# THC-schematic.net
KiCad netlist of a schematic drawn in EAGLE
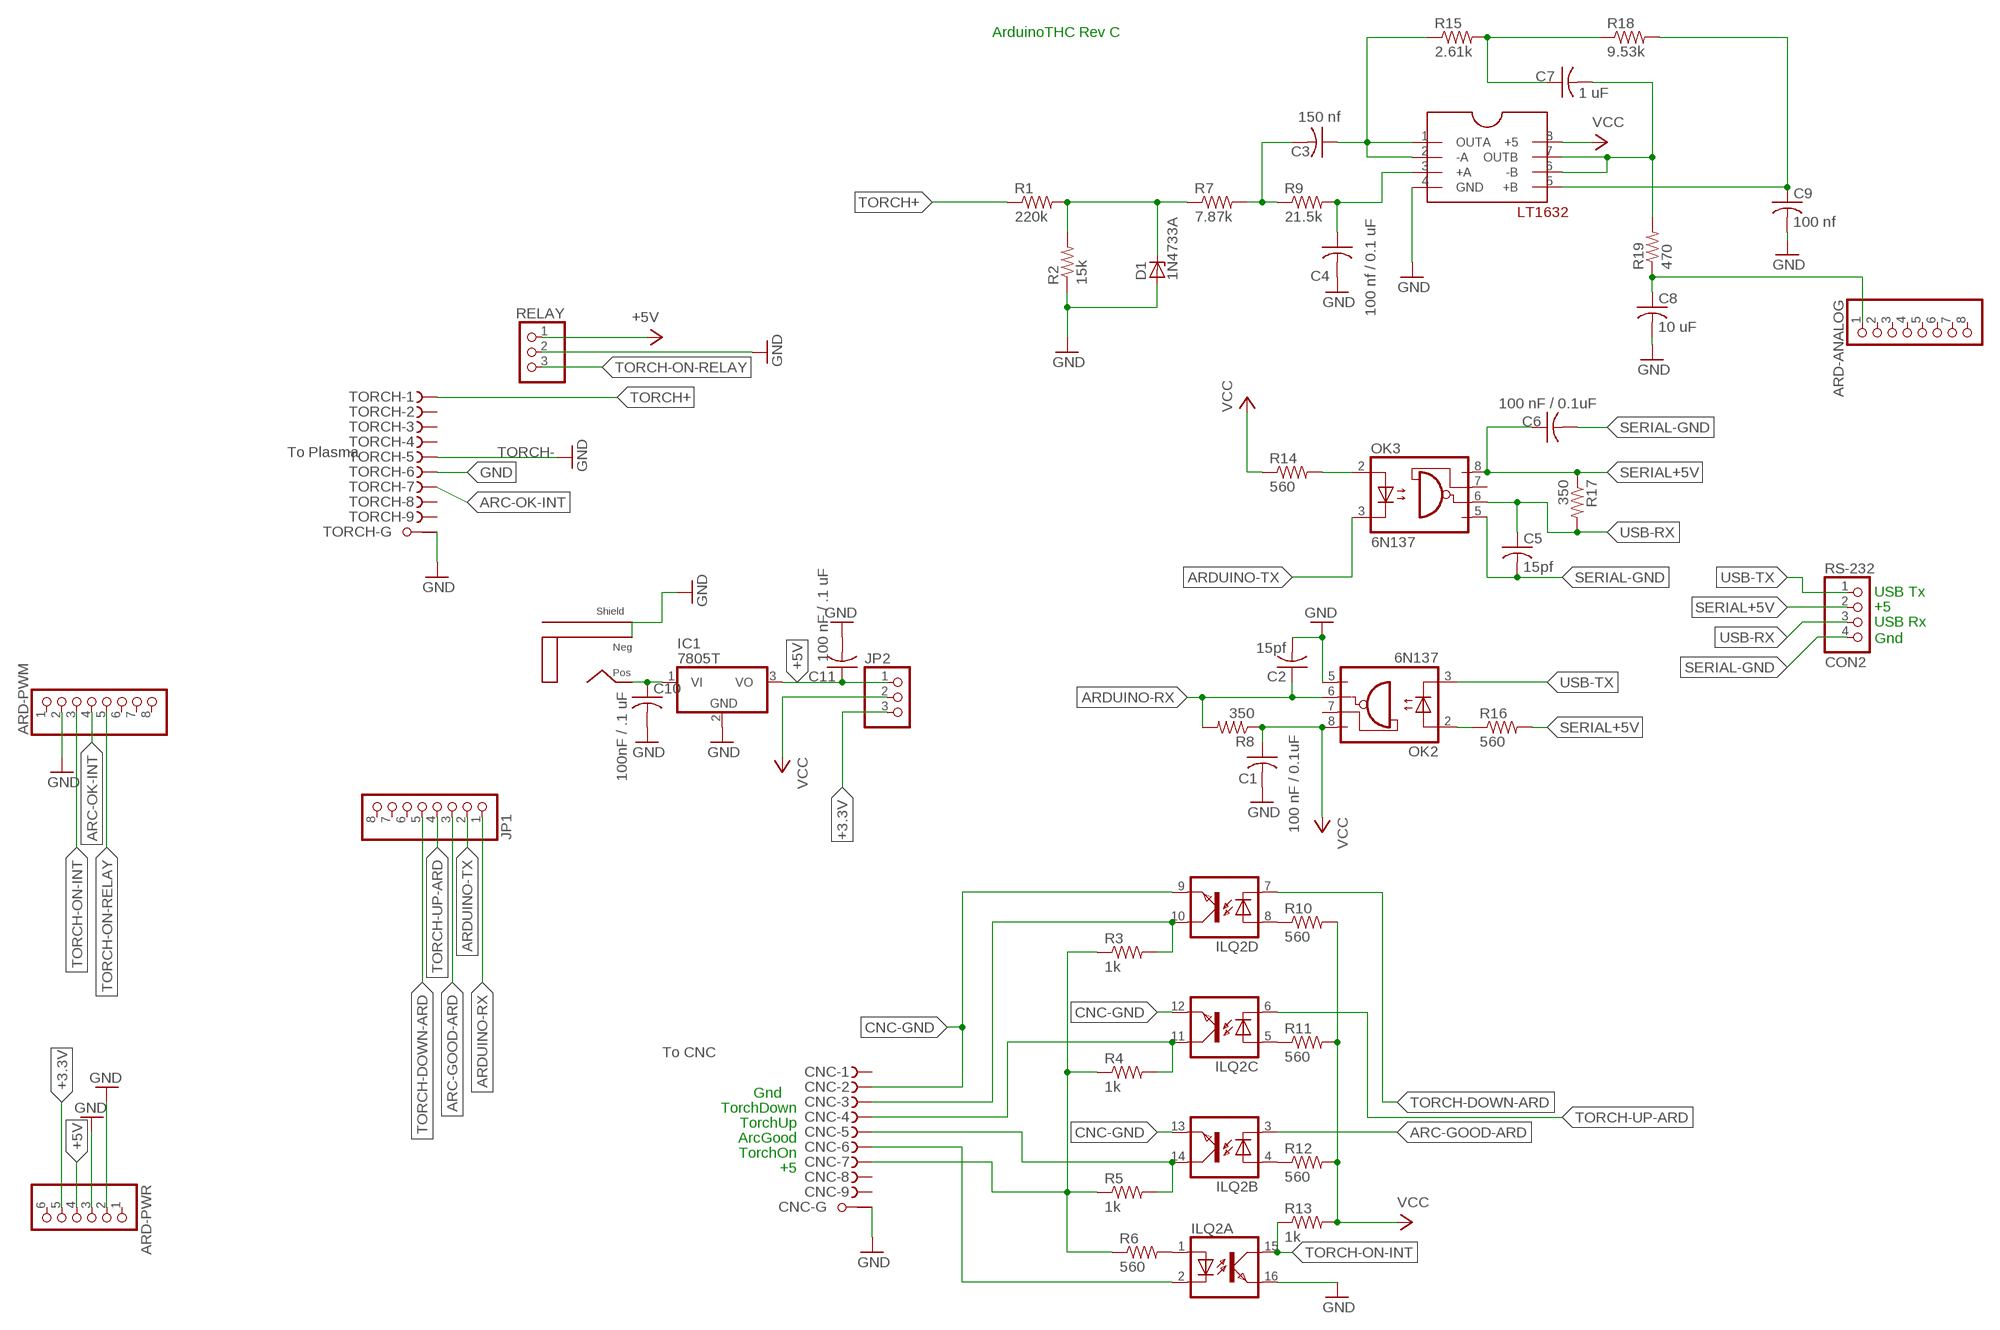
[diagram p0: schematic, sheet 1]

(export (version "E")
  (design (tool "Eeschema 10.0.6"))
  (components
    (comp (ref "ARD-ANALOG")
      (value "PINHD-1X8")
      (footprint "eagle-import:1X08")
      (libsource (lib "eagle-import") (part "PINHD-1X8"))
    )
    (comp (ref "ARD-PWM")
      (value "PINHD-1X8")
      (footprint "eagle-import:1X08")
      (libsource (lib "eagle-import") (part "PINHD-1X8"))
    )
    (comp (ref "ARD-PWR")
      (value "PINHD-1X6")
      (footprint "eagle-import:1X06")
      (libsource (lib "eagle-import") (part "PINHD-1X6"))
    )
    (comp (ref "C1")
      (value "100 nF / 0.1uF")
      (footprint "eagle-import:C025-025X050")
      (libsource (lib "eagle-import") (part "C-US025-025X050"))
    )
    (comp (ref "C2")
      (value "15pf")
      (footprint "eagle-import:C025-025X050")
      (libsource (lib "eagle-import") (part "C-US025-025X050"))
    )
    (comp (ref "C3")
      (value "150 nf")
      (footprint "eagle-import:C025-025X050")
      (libsource (lib "eagle-import") (part "C-US025-025X050"))
    )
    (comp (ref "C4")
      (value "100 nf / 0.1 uF")
      (footprint "eagle-import:C025-025X050")
      (libsource (lib "eagle-import") (part "C-US025-025X050"))
    )
    (comp (ref "C5")
      (value "15pf")
      (footprint "eagle-import:C025-025X050")
      (libsource (lib "eagle-import") (part "C-US025-025X050"))
    )
    (comp (ref "C6")
      (value "100 nF / 0.1uF")
      (footprint "eagle-import:C025-025X050")
      (libsource (lib "eagle-import") (part "C-US025-025X050"))
    )
    (comp (ref "C7")
      (value "1 uF")
      (footprint "eagle-import:C025-025X050")
      (libsource (lib "eagle-import") (part "C-US025-025X050"))
    )
    (comp (ref "C8")
      (value "10 uF")
      (footprint "eagle-import:C025-025X050")
      (libsource (lib "eagle-import") (part "C-US025-025X050"))
    )
    (comp (ref "C9")
      (value "100 nf")
      (footprint "eagle-import:C025-025X050")
      (libsource (lib "eagle-import") (part "C-US025-025X050"))
    )
    (comp (ref "C10")
      (value "100nF / .1 uF")
      (footprint "eagle-import:C025-025X050")
      (libsource (lib "eagle-import") (part "C-US025-025X050"))
    )
    (comp (ref "C11")
      (value "100 nF / .1 uF")
      (footprint "eagle-import:C025-025X050")
      (libsource (lib "eagle-import") (part "C-US025-025X050"))
    )
    (comp (ref "CNC")
      (value "F09HPS")
      (footprint "eagle-import:F09HP")
      (libsource (lib "eagle-import") (part "F09HPS"))
    )
    (comp (ref "D1")
      (value "1N4733A")
      (footprint "eagle-import:DO41Z10")
      (libsource (lib "eagle-import") (part "ZPY"))
    )
    (comp (ref "IC1")
      (value "7805T")
      (footprint "eagle-import:TO220H")
      (libsource (lib "eagle-import") (part "78T05"))
    )
    (comp (ref "ILQ2")
      (value "ILQ1")
      (footprint "eagle-import:DIL16")
      (fields (field (name "MF") "VISHAY/TELEFUNKEN"))
      (libsource (lib "eagle-import") (part "ILQ1"))
    )
    (comp (ref "J1")
      (value "2.1MM-PLUG-PCB-MNT")
      (footprint "eagle-import:2.1MM-PLUG")
      (libsource (lib "eagle-import") (part "2.1MM-PLUG-PCB-MNT"))
    )
    (comp (ref "JP1")
      (value "PINHD-1X8")
      (footprint "eagle-import:1X08")
      (libsource (lib "eagle-import") (part "PINHD-1X8"))
    )
    (comp (ref "JP2")
      (value "PINHD-1X3")
      (footprint "eagle-import:1X03")
      (libsource (lib "eagle-import") (part "PINHD-1X3"))
    )
    (comp (ref "OK2")
      (value "6N137")
      (footprint "eagle-import:DIL08")
      (libsource (lib "eagle-import") (part "6N137"))
    )
    (comp (ref "OK3")
      (value "6N137")
      (footprint "eagle-import:DIL08")
      (libsource (lib "eagle-import") (part "6N137"))
    )
    (comp (ref "R1")
      (value "220k")
      (footprint "eagle-import:0207_7")
      (libsource (lib "eagle-import") (part "R-US_0207/7"))
    )
    (comp (ref "R2")
      (value "15k")
      (footprint "eagle-import:0207_7")
      (libsource (lib "eagle-import") (part "R-US_0207/7"))
    )
    (comp (ref "R3")
      (value "1k")
      (footprint "eagle-import:0207_7")
      (libsource (lib "eagle-import") (part "R-US_0207/7"))
    )
    (comp (ref "R4")
      (value "1k")
      (footprint "eagle-import:0207_7")
      (libsource (lib "eagle-import") (part "R-US_0207/7"))
    )
    (comp (ref "R5")
      (value "1k")
      (footprint "eagle-import:0207_7")
      (libsource (lib "eagle-import") (part "R-US_0207/7"))
    )
    (comp (ref "R6")
      (value "560")
      (footprint "eagle-import:0207_7")
      (libsource (lib "eagle-import") (part "R-US_0207/7"))
    )
    (comp (ref "R7")
      (value "7.87k")
      (footprint "eagle-import:0207_7")
      (libsource (lib "eagle-import") (part "R-US_0207/7"))
    )
    (comp (ref "R8")
      (value "350")
      (footprint "eagle-import:0207_7")
      (libsource (lib "eagle-import") (part "R-US_0207/7"))
    )
    (comp (ref "R9")
      (value "21.5k")
      (footprint "eagle-import:0207_7")
      (libsource (lib "eagle-import") (part "R-US_0207/7"))
    )
    (comp (ref "R10")
      (value "560")
      (footprint "eagle-import:0207_7")
      (libsource (lib "eagle-import") (part "R-US_0207/7"))
    )
    (comp (ref "R11")
      (value "560")
      (footprint "eagle-import:0207_7")
      (libsource (lib "eagle-import") (part "R-US_0207/7"))
    )
    (comp (ref "R12")
      (value "560")
      (footprint "eagle-import:0207_7")
      (libsource (lib "eagle-import") (part "R-US_0207/7"))
    )
    (comp (ref "R13")
      (value "1k")
      (footprint "eagle-import:0207_7")
      (libsource (lib "eagle-import") (part "R-US_0207/7"))
    )
    (comp (ref "R14")
      (value "560")
      (footprint "eagle-import:0207_7")
      (libsource (lib "eagle-import") (part "R-US_0207/7"))
    )
    (comp (ref "R15")
      (value "2.61k")
      (footprint "eagle-import:0207_7")
      (libsource (lib "eagle-import") (part "R-US_0207/7"))
    )
    (comp (ref "R16")
      (value "560")
      (footprint "eagle-import:0207_7")
      (libsource (lib "eagle-import") (part "R-US_0207/7"))
    )
    (comp (ref "R17")
      (value "350")
      (footprint "eagle-import:0207_7")
      (libsource (lib "eagle-import") (part "R-US_0207/7"))
    )
    (comp (ref "R18")
      (value "9.53k")
      (footprint "eagle-import:0207_7")
      (libsource (lib "eagle-import") (part "R-US_0207/7"))
    )
    (comp (ref "R19")
      (value "470")
      (footprint "eagle-import:0207_7")
      (libsource (lib "eagle-import") (part "R-US_0207/7"))
    )
    (comp (ref "RELAY")
      (value "PINHD-1X3")
      (footprint "eagle-import:1X03")
      (libsource (lib "eagle-import") (part "PINHD-1X3"))
    )
    (comp (ref "RS-232")
      (value "CON2")
      (footprint "eagle-import:1X04")
      (libsource (lib "eagle-import") (part "PINHD-1X4"))
    )
    (comp (ref "TORCH")
      (value "F09HPS")
      (footprint "eagle-import:F09HP")
      (libsource (lib "eagle-import") (part "F09HPS"))
    )
    (comp (ref "U$1")
      (value "LT1632")
      (footprint "eagle-import:DIP08")
      (libsource (lib "eagle-import") (part "LT1632"))
    )
  )
  (nets
    (net (code "1") (name "+3.3V") (class "Default")
      (node (ref "ARD-PWR") (pin "5") (pinfunction "5_5") (pintype "passive"))
      (node (ref "JP2") (pin "3") (pinfunction "3_3") (pintype "passive"))
    )
    (net (code "2") (name "+5V") (class "Default")
      (node (ref "ARD-PWR") (pin "4") (pinfunction "4_4") (pintype "passive"))
      (node (ref "C11") (pin "1") (pinfunction "1_1") (pintype "passive"))
      (node (ref "IC1") (pin "3") (pinfunction "VO_3") (pintype "passive"))
      (node (ref "JP2") (pin "1") (pinfunction "1_1") (pintype "passive"))
      (node (ref "RELAY") (pin "1") (pinfunction "1_1") (pintype "passive"))
    )
    (net (code "3") (name "ARC-GOOD-ARD") (class "Default")
      (node (ref "ILQ2") (pin "3") (pinfunction "C_3") (pintype "passive"))
      (node (ref "JP1") (pin "3") (pinfunction "3_3") (pintype "passive"))
    )
    (net (code "4") (name "ARC-OK-INT") (class "Default")
      (node (ref "ARD-PWM") (pin "4") (pinfunction "4_4") (pintype "passive"))
      (node (ref "TORCH") (pin "7") (pinfunction "F_7") (pintype "passive"))
    )
    (net (code "5") (name "ARDUINO-RX") (class "Default")
      (node (ref "C2") (pin "1") (pinfunction "1_1") (pintype "passive"))
      (node (ref "JP1") (pin "1") (pinfunction "1_1") (pintype "passive"))
      (node (ref "OK2") (pin "6") (pinfunction "VO_6") (pintype "passive"))
      (node (ref "R8") (pin "2") (pinfunction "2_2") (pintype "passive"))
    )
    (net (code "6") (name "ARDUINO-TX") (class "Default")
      (node (ref "JP1") (pin "2") (pinfunction "2_2") (pintype "passive"))
      (node (ref "OK3") (pin "3") (pinfunction "C_3") (pintype "passive"))
    )
    (net (code "7") (name "CNC-GND") (class "Default")
      (node (ref "CNC") (pin "2") (pinfunction "F_2") (pintype "passive"))
      (node (ref "ILQ2") (pin "12") (pinfunction "EMIT_12") (pintype "passive"))
      (node (ref "ILQ2") (pin "13") (pinfunction "EMIT_13") (pintype "passive"))
      (node (ref "ILQ2") (pin "9") (pinfunction "EMIT_9") (pintype "passive"))
    )
    (net (code "8") (name "GND") (class "Default")
      (node (ref "ARD-PWM") (pin "2") (pinfunction "2_2") (pintype "passive"))
      (node (ref "ARD-PWR") (pin "2") (pinfunction "2_2") (pintype "passive"))
      (node (ref "ARD-PWR") (pin "3") (pinfunction "3_3") (pintype "passive"))
      (node (ref "C1") (pin "2") (pinfunction "2_2") (pintype "passive"))
      (node (ref "C10") (pin "2") (pinfunction "2_2") (pintype "passive"))
      (node (ref "C11") (pin "2") (pinfunction "2_2") (pintype "passive"))
      (node (ref "C2") (pin "2") (pinfunction "2_2") (pintype "passive"))
      (node (ref "C4") (pin "2") (pinfunction "2_2") (pintype "passive"))
      (node (ref "C8") (pin "2") (pinfunction "2_2") (pintype "passive"))
      (node (ref "C9") (pin "2") (pinfunction "2_2") (pintype "passive"))
      (node (ref "CNC") (pin "G1") (pinfunction "G1_G1") (pintype "passive"))
      (node (ref "D1") (pin "A") (pinfunction "A_A") (pintype "passive"))
      (node (ref "IC1") (pin "2") (pinfunction "GND_2") (pintype "passive"))
      (node (ref "ILQ2") (pin "16") (pinfunction "EMIT_16") (pintype "passive"))
      (node (ref "J1") (pin "P$NEG") (pinfunction "P$NEG_P$NEG") (pintype "bidirectional"))
      (node (ref "J1") (pin "P$SHLD") (pinfunction "P$SHLD_P$SHLD") (pintype "bidirectional"))
      (node (ref "OK2") (pin "5") (pinfunction "GND_5") (pintype "passive"))
      (node (ref "R2") (pin "1") (pinfunction "1_1") (pintype "passive"))
      (node (ref "RELAY") (pin "2") (pinfunction "2_2") (pintype "passive"))
      (node (ref "TORCH") (pin "5") (pinfunction "F_5") (pintype "passive"))
      (node (ref "TORCH") (pin "6") (pinfunction "F_6") (pintype "passive"))
      (node (ref "TORCH") (pin "G1") (pinfunction "G1_G1") (pintype "passive"))
      (node (ref "U$1") (pin "4") (pinfunction "GND_4") (pintype "bidirectional"))
    )
    (net (code "9") (name "Net-(ARD-ANALOG-Pad1)") (class "Default")
      (node (ref "ARD-ANALOG") (pin "1") (pinfunction "1_1") (pintype "passive"))
      (node (ref "C8") (pin "1") (pinfunction "1_1") (pintype "passive"))
      (node (ref "R19") (pin "1") (pinfunction "1_1") (pintype "passive"))
    )
    (net (code "10") (name "Net-(C3-Pad2)") (class "Default")
      (node (ref "C3") (pin "2") (pinfunction "2_2") (pintype "passive"))
      (node (ref "R7") (pin "2") (pinfunction "2_2") (pintype "passive"))
      (node (ref "R9") (pin "1") (pinfunction "1_1") (pintype "passive"))
    )
    (net (code "11") (name "Net-(C7-Pad1)") (class "Default")
      (node (ref "C7") (pin "1") (pinfunction "1_1") (pintype "passive"))
      (node (ref "R15") (pin "2") (pinfunction "2_2") (pintype "passive"))
      (node (ref "R18") (pin "1") (pinfunction "1_1") (pintype "passive"))
    )
    (net (code "12") (name "Net-(CNCC-F)") (class "Default")
      (node (ref "CNC") (pin "3") (pinfunction "F_3") (pintype "passive"))
      (node (ref "ILQ2") (pin "10") (pinfunction "COL_10") (pintype "passive"))
      (node (ref "R3") (pin "2") (pinfunction "2_2") (pintype "passive"))
    )
    (net (code "13") (name "Net-(CNCD-F)") (class "Default")
      (node (ref "CNC") (pin "4") (pinfunction "F_4") (pintype "passive"))
      (node (ref "ILQ2") (pin "11") (pinfunction "COL_11") (pintype "passive"))
      (node (ref "R4") (pin "2") (pinfunction "2_2") (pintype "passive"))
    )
    (net (code "14") (name "Net-(CNCE-F)") (class "Default")
      (node (ref "CNC") (pin "5") (pinfunction "F_5") (pintype "passive"))
      (node (ref "ILQ2") (pin "14") (pinfunction "COL_14") (pintype "passive"))
      (node (ref "R5") (pin "2") (pinfunction "2_2") (pintype "passive"))
    )
    (net (code "15") (name "Net-(CNCF-F)") (class "Default")
      (node (ref "CNC") (pin "6") (pinfunction "F_6") (pintype "passive"))
      (node (ref "ILQ2") (pin "2") (pinfunction "C_2") (pintype "passive"))
    )
    (net (code "16") (name "Net-(CNCG-F)") (class "Default")
      (node (ref "CNC") (pin "7") (pinfunction "F_7") (pintype "passive"))
      (node (ref "R3") (pin "1") (pinfunction "1_1") (pintype "passive"))
      (node (ref "R4") (pin "1") (pinfunction "1_1") (pintype "passive"))
      (node (ref "R5") (pin "1") (pinfunction "1_1") (pintype "passive"))
      (node (ref "R6") (pin "1") (pinfunction "1_1") (pintype "passive"))
    )
    (net (code "17") (name "Net-(D1-PadC)") (class "Default")
      (node (ref "D1") (pin "C") (pinfunction "C_C") (pintype "passive"))
      (node (ref "R1") (pin "2") (pinfunction "2_2") (pintype "passive"))
      (node (ref "R2") (pin "2") (pinfunction "2_2") (pintype "passive"))
      (node (ref "R7") (pin "1") (pinfunction "1_1") (pintype "passive"))
    )
    (net (code "18") (name "Net-(IC1-VI)") (class "Default")
      (node (ref "C10") (pin "1") (pinfunction "1_1") (pintype "passive"))
      (node (ref "IC1") (pin "1") (pinfunction "VI_1") (pintype "input"))
      (node (ref "J1") (pin "P$POS") (pinfunction "P$POS_P$POS") (pintype "bidirectional"))
    )
    (net (code "19") (name "Net-(ILQ2A-A)") (class "Default")
      (node (ref "ILQ2") (pin "1") (pinfunction "A_1") (pintype "passive"))
      (node (ref "R6") (pin "2") (pinfunction "2_2") (pintype "passive"))
    )
    (net (code "20") (name "Net-(ILQ2B-A)") (class "Default")
      (node (ref "ILQ2") (pin "4") (pinfunction "A_4") (pintype "passive"))
      (node (ref "R12") (pin "1") (pinfunction "1_1") (pintype "passive"))
    )
    (net (code "21") (name "Net-(ILQ2C-A)") (class "Default")
      (node (ref "ILQ2") (pin "5") (pinfunction "A_5") (pintype "passive"))
      (node (ref "R11") (pin "1") (pinfunction "1_1") (pintype "passive"))
    )
    (net (code "22") (name "Net-(ILQ2D-A)") (class "Default")
      (node (ref "ILQ2") (pin "8") (pinfunction "A_8") (pintype "passive"))
      (node (ref "R10") (pin "1") (pinfunction "1_1") (pintype "passive"))
    )
    (net (code "23") (name "Net-(OK2-A)") (class "Default")
      (node (ref "OK2") (pin "2") (pinfunction "A_2") (pintype "passive"))
      (node (ref "R16") (pin "1") (pinfunction "1_1") (pintype "passive"))
    )
    (net (code "24") (name "Net-(OK3-A)") (class "Default")
      (node (ref "OK3") (pin "2") (pinfunction "A_2") (pintype "passive"))
      (node (ref "R14") (pin "2") (pinfunction "2_2") (pintype "passive"))
    )
    (net (code "25") (name "Net-(U$1-+A)") (class "Default")
      (node (ref "C4") (pin "1") (pinfunction "1_1") (pintype "passive"))
      (node (ref "R9") (pin "2") (pinfunction "2_2") (pintype "passive"))
      (node (ref "U$1") (pin "3") (pinfunction "+A_3") (pintype "bidirectional"))
    )
    (net (code "26") (name "Net-(U$1-+B)") (class "Default")
      (node (ref "C9") (pin "1") (pinfunction "1_1") (pintype "passive"))
      (node (ref "R18") (pin "2") (pinfunction "2_2") (pintype "passive"))
      (node (ref "U$1") (pin "5") (pinfunction "+B_5") (pintype "bidirectional"))
    )
    (net (code "27") (name "Net-(U$1--A)") (class "Default")
      (node (ref "C3") (pin "1") (pinfunction "1_1") (pintype "passive"))
      (node (ref "R15") (pin "1") (pinfunction "1_1") (pintype "passive"))
      (node (ref "U$1") (pin "1") (pinfunction "OUTA_1") (pintype "bidirectional"))
      (node (ref "U$1") (pin "2") (pinfunction "-A_2") (pintype "bidirectional"))
    )
    (net (code "28") (name "Net-(U$1--B)") (class "Default")
      (node (ref "C7") (pin "2") (pinfunction "2_2") (pintype "passive"))
      (node (ref "R19") (pin "2") (pinfunction "2_2") (pintype "passive"))
      (node (ref "U$1") (pin "6") (pinfunction "-B_6") (pintype "bidirectional"))
      (node (ref "U$1") (pin "7") (pinfunction "OUTB_7") (pintype "bidirectional"))
    )
    (net (code "29") (name "SERIAL+5V") (class "Default")
      (node (ref "C6") (pin "1") (pinfunction "1_1") (pintype "passive"))
      (node (ref "OK3") (pin "8") (pinfunction "VCC_8") (pintype "passive"))
      (node (ref "R16") (pin "2") (pinfunction "2_2") (pintype "passive"))
      (node (ref "R17") (pin "1") (pinfunction "1_1") (pintype "passive"))
      (node (ref "RS-232") (pin "2") (pinfunction "2_2") (pintype "passive"))
    )
    (net (code "30") (name "SERIAL-GND") (class "Default")
      (node (ref "C5") (pin "2") (pinfunction "2_2") (pintype "passive"))
      (node (ref "C6") (pin "2") (pinfunction "2_2") (pintype "passive"))
      (node (ref "OK3") (pin "5") (pinfunction "GND_5") (pintype "passive"))
      (node (ref "RS-232") (pin "4") (pinfunction "4_4") (pintype "passive"))
    )
    (net (code "31") (name "TORCH+") (class "Default")
      (node (ref "R1") (pin "1") (pinfunction "1_1") (pintype "passive"))
      (node (ref "TORCH") (pin "1") (pinfunction "F_1") (pintype "passive"))
    )
    (net (code "32") (name "TORCH-DOWN-ARD") (class "Default")
      (node (ref "ILQ2") (pin "7") (pinfunction "C_7") (pintype "passive"))
      (node (ref "JP1") (pin "5") (pinfunction "5_5") (pintype "passive"))
    )
    (net (code "33") (name "TORCH-ON-INT") (class "Default")
      (node (ref "ARD-PWM") (pin "3") (pinfunction "3_3") (pintype "passive"))
      (node (ref "ILQ2") (pin "15") (pinfunction "COL_15") (pintype "passive"))
      (node (ref "R13") (pin "1") (pinfunction "1_1") (pintype "passive"))
    )
    (net (code "34") (name "TORCH-ON-RELAY") (class "Default")
      (node (ref "ARD-PWM") (pin "5") (pinfunction "5_5") (pintype "passive"))
      (node (ref "RELAY") (pin "3") (pinfunction "3_3") (pintype "passive"))
    )
    (net (code "35") (name "TORCH-UP-ARD") (class "Default")
      (node (ref "ILQ2") (pin "6") (pinfunction "C_6") (pintype "passive"))
      (node (ref "JP1") (pin "4") (pinfunction "4_4") (pintype "passive"))
    )
    (net (code "36") (name "USB-RX") (class "Default")
      (node (ref "C5") (pin "1") (pinfunction "1_1") (pintype "passive"))
      (node (ref "OK3") (pin "6") (pinfunction "VO_6") (pintype "passive"))
      (node (ref "R17") (pin "2") (pinfunction "2_2") (pintype "passive"))
      (node (ref "RS-232") (pin "3") (pinfunction "3_3") (pintype "passive"))
    )
    (net (code "37") (name "USB-TX") (class "Default")
      (node (ref "OK2") (pin "3") (pinfunction "C_3") (pintype "passive"))
      (node (ref "RS-232") (pin "1") (pinfunction "1_1") (pintype "passive"))
    )
    (net (code "38") (name "VCC") (class "Default")
      (node (ref "C1") (pin "1") (pinfunction "1_1") (pintype "passive"))
      (node (ref "JP2") (pin "2") (pinfunction "2_2") (pintype "passive"))
      (node (ref "OK2") (pin "8") (pinfunction "VCC_8") (pintype "passive"))
      (node (ref "R10") (pin "2") (pinfunction "2_2") (pintype "passive"))
      (node (ref "R11") (pin "2") (pinfunction "2_2") (pintype "passive"))
      (node (ref "R12") (pin "2") (pinfunction "2_2") (pintype "passive"))
      (node (ref "R13") (pin "2") (pinfunction "2_2") (pintype "passive"))
      (node (ref "R14") (pin "1") (pinfunction "1_1") (pintype "passive"))
      (node (ref "R8") (pin "1") (pinfunction "1_1") (pintype "passive"))
      (node (ref "U$1") (pin "8") (pinfunction "+5_8") (pintype "bidirectional"))
    )
    (net (code "39") (name "unconnected-(ARD-ANALOG-Pad2)") (class "Default")
      (node (ref "ARD-ANALOG") (pin "2") (pinfunction "2_2") (pintype "passive"))
    )
    (net (code "40") (name "unconnected-(ARD-ANALOG-Pad3)") (class "Default")
      (node (ref "ARD-ANALOG") (pin "3") (pinfunction "3_3") (pintype "passive"))
    )
    (net (code "41") (name "unconnected-(ARD-ANALOG-Pad4)") (class "Default")
      (node (ref "ARD-ANALOG") (pin "4") (pinfunction "4_4") (pintype "passive"))
    )
    (net (code "42") (name "unconnected-(ARD-ANALOG-Pad5)") (class "Default")
      (node (ref "ARD-ANALOG") (pin "5") (pinfunction "5_5") (pintype "passive"))
    )
    (net (code "43") (name "unconnected-(ARD-ANALOG-Pad6)") (class "Default")
      (node (ref "ARD-ANALOG") (pin "6") (pinfunction "6_6") (pintype "passive"))
    )
    (net (code "44") (name "unconnected-(ARD-ANALOG-Pad7)") (class "Default")
      (node (ref "ARD-ANALOG") (pin "7") (pinfunction "7_7") (pintype "passive"))
    )
    (net (code "45") (name "unconnected-(ARD-ANALOG-Pad8)") (class "Default")
      (node (ref "ARD-ANALOG") (pin "8") (pinfunction "8_8") (pintype "passive"))
    )
    (net (code "46") (name "unconnected-(ARD-PWM-Pad1)") (class "Default")
      (node (ref "ARD-PWM") (pin "1") (pinfunction "1_1") (pintype "passive"))
    )
    (net (code "47") (name "unconnected-(ARD-PWM-Pad6)") (class "Default")
      (node (ref "ARD-PWM") (pin "6") (pinfunction "6_6") (pintype "passive"))
    )
    (net (code "48") (name "unconnected-(ARD-PWM-Pad7)") (class "Default")
      (node (ref "ARD-PWM") (pin "7") (pinfunction "7_7") (pintype "passive"))
    )
    (net (code "49") (name "unconnected-(ARD-PWM-Pad8)") (class "Default")
      (node (ref "ARD-PWM") (pin "8") (pinfunction "8_8") (pintype "passive"))
    )
    (net (code "50") (name "unconnected-(ARD-PWR-Pad1)") (class "Default")
      (node (ref "ARD-PWR") (pin "1") (pinfunction "1_1") (pintype "passive"))
    )
    (net (code "51") (name "unconnected-(ARD-PWR-Pad6)") (class "Default")
      (node (ref "ARD-PWR") (pin "6") (pinfunction "6_6") (pintype "passive"))
    )
    (net (code "52") (name "unconnected-(CNC-PadG2)") (class "Default")
      (node (ref "CNC") (pin "G2") (pinfunction "G2_G2") (pintype "passive"))
    )
    (net (code "53") (name "unconnected-(CNCA-F-Pad1)") (class "Default")
      (node (ref "CNC") (pin "1") (pinfunction "F_1") (pintype "passive"))
    )
    (net (code "54") (name "unconnected-(CNCH-F-Pad8)") (class "Default")
      (node (ref "CNC") (pin "8") (pinfunction "F_8") (pintype "passive"))
    )
    (net (code "55") (name "unconnected-(CNCI-F-Pad9)") (class "Default")
      (node (ref "CNC") (pin "9") (pinfunction "F_9") (pintype "passive"))
    )
    (net (code "56") (name "unconnected-(JP1-Pad6)") (class "Default")
      (node (ref "JP1") (pin "6") (pinfunction "6_6") (pintype "passive"))
    )
    (net (code "57") (name "unconnected-(JP1-Pad7)") (class "Default")
      (node (ref "JP1") (pin "7") (pinfunction "7_7") (pintype "passive"))
    )
    (net (code "58") (name "unconnected-(JP1-Pad8)") (class "Default")
      (node (ref "JP1") (pin "8") (pinfunction "8_8") (pintype "passive"))
    )
    (net (code "59") (name "unconnected-(OK2-VE-Pad7)") (class "Default")
      (node (ref "OK2") (pin "7") (pinfunction "VE_7") (pintype "passive"))
    )
    (net (code "60") (name "unconnected-(OK3-VE-Pad7)") (class "Default")
      (node (ref "OK3") (pin "7") (pinfunction "VE_7") (pintype "passive"))
    )
    (net (code "61") (name "unconnected-(TORCH-PadG2)") (class "Default")
      (node (ref "TORCH") (pin "G2") (pinfunction "G2_G2") (pintype "passive"))
    )
    (net (code "62") (name "unconnected-(TORCHB-F-Pad2)") (class "Default")
      (node (ref "TORCH") (pin "2") (pinfunction "F_2") (pintype "passive"))
    )
    (net (code "63") (name "unconnected-(TORCHC-F-Pad3)") (class "Default")
      (node (ref "TORCH") (pin "3") (pinfunction "F_3") (pintype "passive"))
    )
    (net (code "64") (name "unconnected-(TORCHD-F-Pad4)") (class "Default")
      (node (ref "TORCH") (pin "4") (pinfunction "F_4") (pintype "passive"))
    )
    (net (code "65") (name "unconnected-(TORCHH-F-Pad8)") (class "Default")
      (node (ref "TORCH") (pin "8") (pinfunction "F_8") (pintype "passive"))
    )
    (net (code "66") (name "unconnected-(TORCHI-F-Pad9)") (class "Default")
      (node (ref "TORCH") (pin "9") (pinfunction "F_9") (pintype "passive"))
    )
  )
)
